# PROIECT_v21.net
KiCad netlist of a schematic drawn in EAGLE
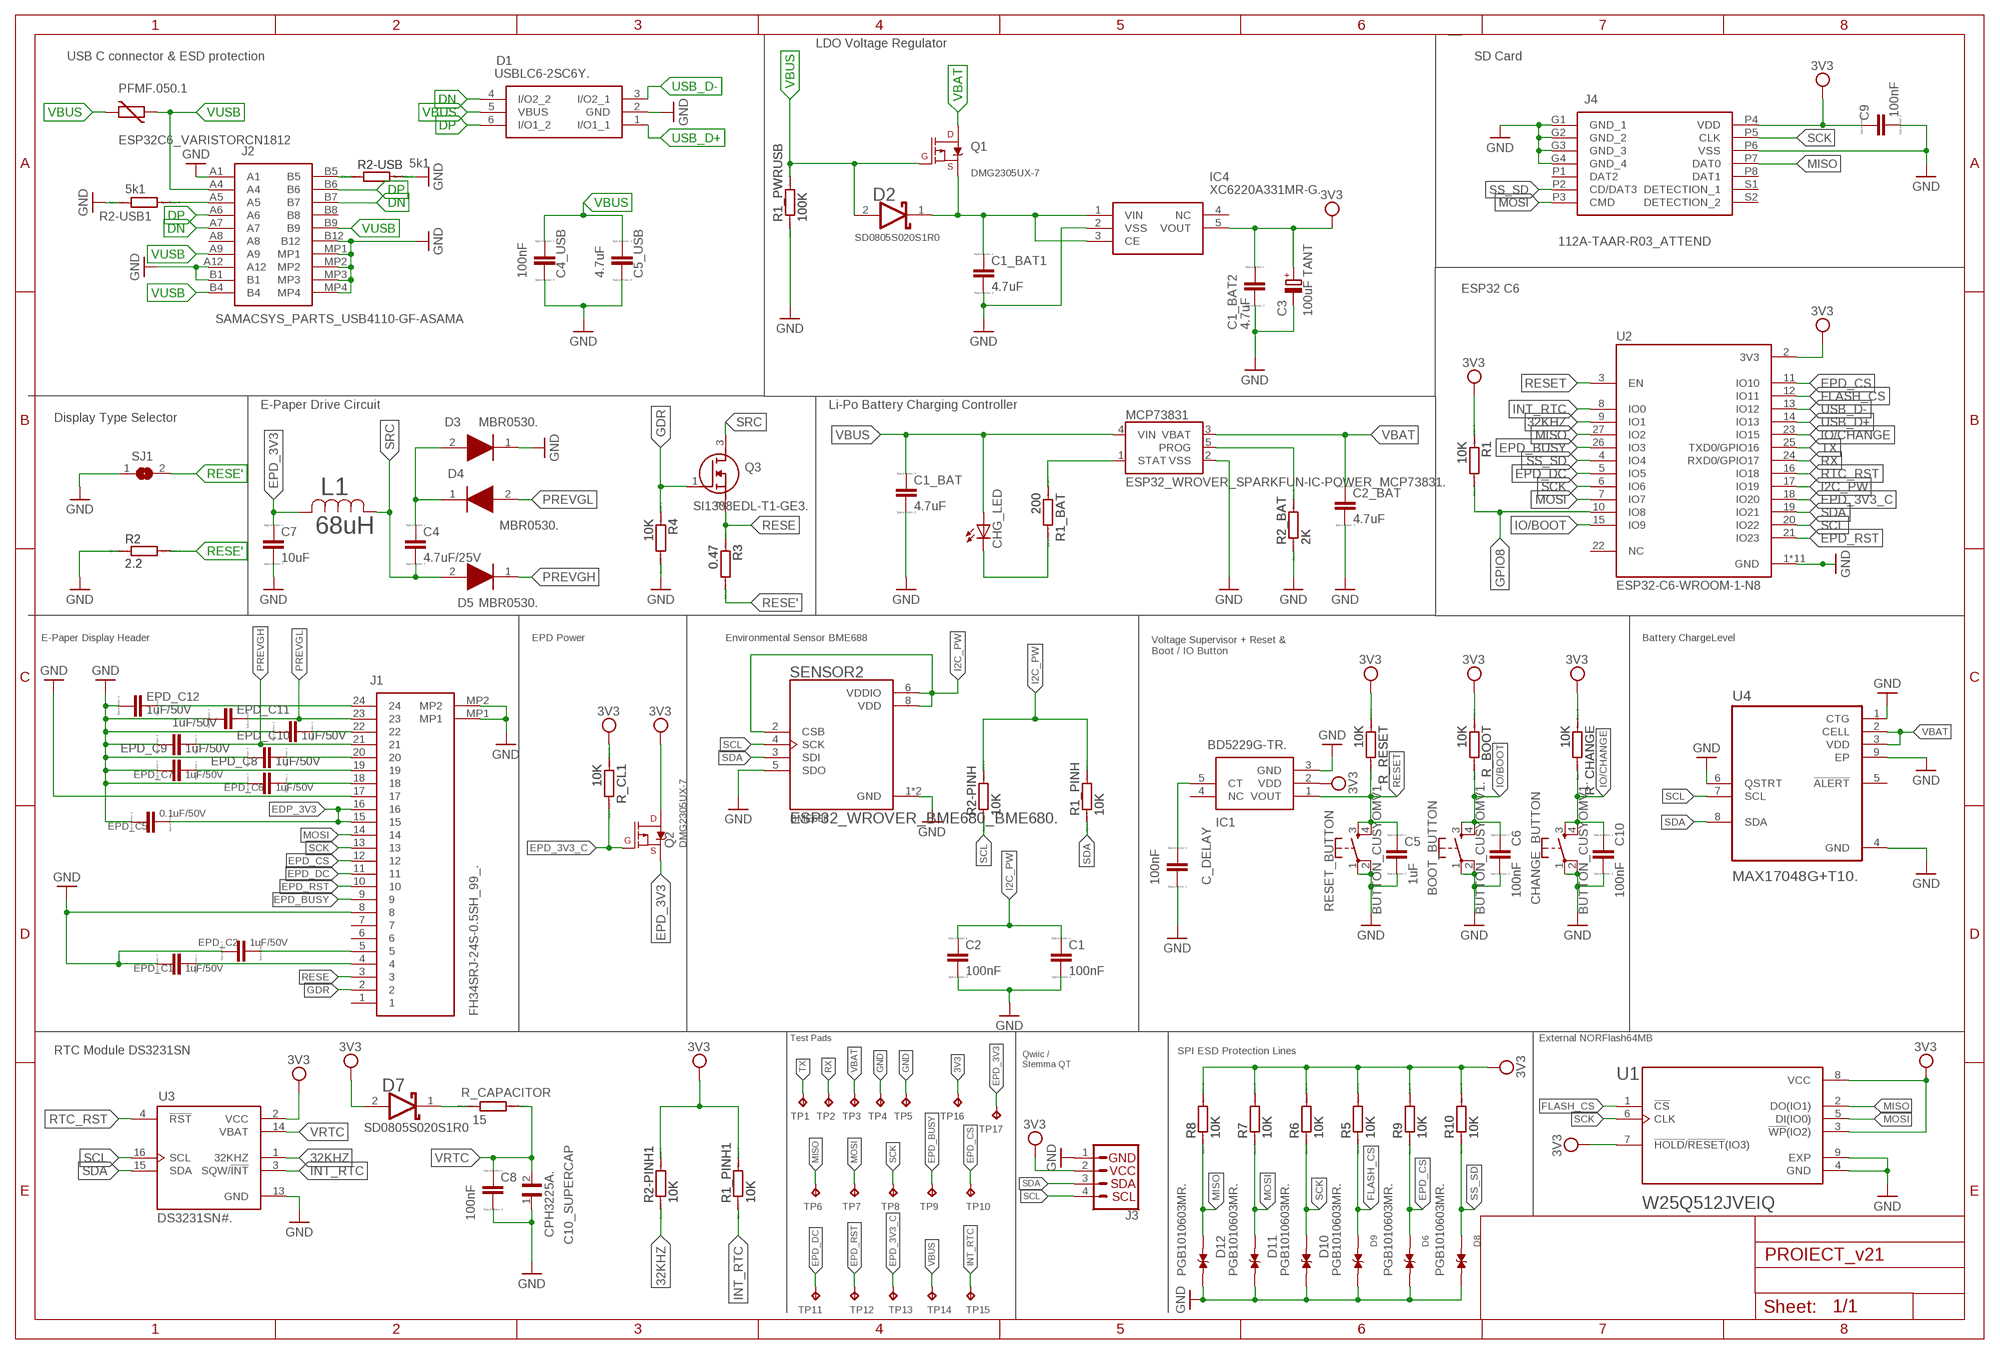
[diagram p0: schematic, sheet 1]

(export (version "E")
  (design (tool "Eeschema 10.0.6"))
  (components
    (comp (ref "BOOT_BUTTON")
      (value "BUTTON_CUSYOMV1.")
      (footprint "eagle-import:MYBUTTON")
      (libsource (lib "eagle-import") (part "BUTTON_CUSYOMV1."))
    )
    (comp (ref "C1")
      (value "100nF")
      (footprint "eagle-import:EAGLE-LTSPICE_C0402")
      (libsource (lib "eagle-import") (part "EAGLE-LTSPICE_CC0402"))
    )
    (comp (ref "C1_BAT")
      (value "4.7uF")
      (footprint "eagle-import:EAGLE-LTSPICE_C0402")
      (libsource (lib "eagle-import") (part "EAGLE-LTSPICE_CC0402"))
    )
    (comp (ref "C1_BAT1")
      (value "4.7uF")
      (footprint "eagle-import:EAGLE-LTSPICE_C0402")
      (libsource (lib "eagle-import") (part "EAGLE-LTSPICE_CC0402"))
    )
    (comp (ref "C1_BAT2")
      (value "4.7uF")
      (footprint "eagle-import:EAGLE-LTSPICE_C0402")
      (libsource (lib "eagle-import") (part "EAGLE-LTSPICE_CC0402"))
    )
    (comp (ref "C2")
      (value "100nF")
      (footprint "eagle-import:EAGLE-LTSPICE_C0402")
      (libsource (lib "eagle-import") (part "EAGLE-LTSPICE_CC0402"))
    )
    (comp (ref "C2_BAT")
      (value "4.7uF")
      (footprint "eagle-import:EAGLE-LTSPICE_C0402")
      (libsource (lib "eagle-import") (part "EAGLE-LTSPICE_CC0402"))
    )
    (comp (ref "C3")
      (value "100uF TANT")
      (footprint "eagle-import:RCL_CT3528")
      (libsource (lib "eagle-import") (part "RCL_CPOL-EUCT3528"))
    )
    (comp (ref "C4")
      (value "4.7uF/25V")
      (footprint "eagle-import:EAGLE-LTSPICE_C0402")
      (libsource (lib "eagle-import") (part "EAGLE-LTSPICE_CC0402"))
    )
    (comp (ref "C4_USB")
      (value "100nF")
      (footprint "eagle-import:EAGLE-LTSPICE_C0402")
      (libsource (lib "eagle-import") (part "EAGLE-LTSPICE_CC0402"))
    )
    (comp (ref "C5")
      (value "1uF")
      (footprint "eagle-import:EAGLE-LTSPICE_C0402")
      (libsource (lib "eagle-import") (part "EAGLE-LTSPICE_CC0402"))
    )
    (comp (ref "C5_USB")
      (value "4.7uF")
      (footprint "eagle-import:EAGLE-LTSPICE_C0402")
      (libsource (lib "eagle-import") (part "EAGLE-LTSPICE_CC0402"))
    )
    (comp (ref "C6")
      (value "100nF")
      (footprint "eagle-import:EAGLE-LTSPICE_C0402")
      (libsource (lib "eagle-import") (part "EAGLE-LTSPICE_CC0402"))
    )
    (comp (ref "C7")
      (value "10uF")
      (footprint "eagle-import:EAGLE-LTSPICE_C0402")
      (libsource (lib "eagle-import") (part "EAGLE-LTSPICE_CC0402"))
    )
    (comp (ref "C8")
      (value "100nF")
      (footprint "eagle-import:EAGLE-LTSPICE_C0402")
      (libsource (lib "eagle-import") (part "EAGLE-LTSPICE_CC0402"))
    )
    (comp (ref "C9")
      (value "100nF")
      (footprint "eagle-import:EAGLE-LTSPICE_C0402")
      (libsource (lib "eagle-import") (part "EAGLE-LTSPICE_CC0402"))
    )
    (comp (ref "C10")
      (value "100nF")
      (footprint "eagle-import:EAGLE-LTSPICE_C0402")
      (libsource (lib "eagle-import") (part "EAGLE-LTSPICE_CC0402"))
    )
    (comp (ref "C10_SUPERCAP")
      (value "CPH3225A.")
      (footprint "eagle-import:CAPCP3225X100N")
      (libsource (lib "eagle-import") (part "CPH3225A."))
    )
    (comp (ref "CHANGE_BUTTON")
      (value "BUTTON_CUSYOMV1.")
      (footprint "eagle-import:MYBUTTON")
      (libsource (lib "eagle-import") (part "BUTTON_CUSYOMV1."))
    )
    (comp (ref "CHG_LED")
      (value "ADAFRUIT_LEDCHIP-LED0603")
      (footprint "eagle-import:ADAFRUIT_CHIP-LED0603")
      (libsource (lib "eagle-import") (part "ADAFRUIT_LEDCHIP-LED0603"))
    )
    (comp (ref "C_DELAY")
      (value "100nF")
      (footprint "eagle-import:EAGLE-LTSPICE_C0402")
      (libsource (lib "eagle-import") (part "EAGLE-LTSPICE_CC0402"))
    )
    (comp (ref "D1")
      (value "USBLC6-2SC6Y.")
      (footprint "eagle-import:SOT95P280X145-6N")
      (libsource (lib "eagle-import") (part "USBLC6-2SC6Y."))
    )
    (comp (ref "D2")
      (value "ESP32_WROVER_AVX---SD0805S020S1R0_AVX_SD0805S020S1R0_0_0AVX_SD0805S020S1R0_0_0")
      (footprint "eagle-import:ESP32_WROVER_AVX---SD0805S020S1R0_AVX_SD0805S020S1R0_0")
      (fields (field (name "NUME") "SD0805S020S1R0"))
      (libsource (lib "eagle-import") (part "ESP32_WROVER_AVX---SD0805S020S1R0_AVX_SD0805S020S1R0_0_0AVX_SD0805S020S1R0_0_0"))
    )
    (comp (ref "D3")
      (value "MBR0530.")
      (footprint "eagle-import:SOD3716X135N")
      (libsource (lib "eagle-import") (part "MBR0530."))
    )
    (comp (ref "D4")
      (value "MBR0530.")
      (footprint "eagle-import:SOD3716X135N")
      (libsource (lib "eagle-import") (part "MBR0530."))
    )
    (comp (ref "D5")
      (value "MBR0530.")
      (footprint "eagle-import:SOD3716X135N")
      (libsource (lib "eagle-import") (part "MBR0530."))
    )
    (comp (ref "D6")
      (value "PGB1010603MR.")
      (footprint "eagle-import:DIOC1608X36N")
      (libsource (lib "eagle-import") (part "PGB1010603MR."))
    )
    (comp (ref "D7")
      (value "ESP32_WROVER_AVX---SD0805S020S1R0_AVX_SD0805S020S1R0_0_0AVX_SD0805S020S1R0_0_0")
      (footprint "eagle-import:ESP32_WROVER_AVX---SD0805S020S1R0_AVX_SD0805S020S1R0_0")
      (fields (field (name "NUME") "SD0805S020S1R0"))
      (libsource (lib "eagle-import") (part "ESP32_WROVER_AVX---SD0805S020S1R0_AVX_SD0805S020S1R0_0_0AVX_SD0805S020S1R0_0_0"))
    )
    (comp (ref "D8")
      (value "PGB1010603MR.")
      (footprint "eagle-import:DIOC1608X36N")
      (libsource (lib "eagle-import") (part "PGB1010603MR."))
    )
    (comp (ref "D9")
      (value "PGB1010603MR.")
      (footprint "eagle-import:DIOC1608X36N")
      (libsource (lib "eagle-import") (part "PGB1010603MR."))
    )
    (comp (ref "D10")
      (value "PGB1010603MR.")
      (footprint "eagle-import:DIOC1608X36N")
      (libsource (lib "eagle-import") (part "PGB1010603MR."))
    )
    (comp (ref "D11")
      (value "PGB1010603MR.")
      (footprint "eagle-import:DIOC1608X36N")
      (libsource (lib "eagle-import") (part "PGB1010603MR."))
    )
    (comp (ref "D12")
      (value "PGB1010603MR.")
      (footprint "eagle-import:DIOC1608X36N")
      (libsource (lib "eagle-import") (part "PGB1010603MR."))
    )
    (comp (ref "EPD_C1")
      (value "1uF/50V")
      (footprint "eagle-import:EAGLE-LTSPICE_C0402")
      (libsource (lib "eagle-import") (part "EAGLE-LTSPICE_CC0402"))
    )
    (comp (ref "EPD_C2")
      (value "1uF/50V")
      (footprint "eagle-import:EAGLE-LTSPICE_C0402")
      (libsource (lib "eagle-import") (part "EAGLE-LTSPICE_CC0402"))
    )
    (comp (ref "EPD_C5")
      (value "0.1uF/50V")
      (footprint "eagle-import:EAGLE-LTSPICE_C0402")
      (libsource (lib "eagle-import") (part "EAGLE-LTSPICE_CC0402"))
    )
    (comp (ref "EPD_C6")
      (value "1uF/50V")
      (footprint "eagle-import:EAGLE-LTSPICE_C0402")
      (libsource (lib "eagle-import") (part "EAGLE-LTSPICE_CC0402"))
    )
    (comp (ref "EPD_C7")
      (value "1uF/50V")
      (footprint "eagle-import:EAGLE-LTSPICE_C0402")
      (libsource (lib "eagle-import") (part "EAGLE-LTSPICE_CC0402"))
    )
    (comp (ref "EPD_C8")
      (value "1uF/50V")
      (footprint "eagle-import:EAGLE-LTSPICE_C0402")
      (libsource (lib "eagle-import") (part "EAGLE-LTSPICE_CC0402"))
    )
    (comp (ref "EPD_C9")
      (value "1uF/50V")
      (footprint "eagle-import:EAGLE-LTSPICE_C0402")
      (libsource (lib "eagle-import") (part "EAGLE-LTSPICE_CC0402"))
    )
    (comp (ref "EPD_C10")
      (value "1uF/50V")
      (footprint "eagle-import:EAGLE-LTSPICE_C0402")
      (libsource (lib "eagle-import") (part "EAGLE-LTSPICE_CC0402"))
    )
    (comp (ref "EPD_C11")
      (value "1uF/50V")
      (footprint "eagle-import:EAGLE-LTSPICE_C0402")
      (libsource (lib "eagle-import") (part "EAGLE-LTSPICE_CC0402"))
    )
    (comp (ref "EPD_C12")
      (value "1uF/50V")
      (footprint "eagle-import:EAGLE-LTSPICE_C0402")
      (libsource (lib "eagle-import") (part "EAGLE-LTSPICE_CC0402"))
    )
    (comp (ref "IC1")
      (value "BD5229G-TR.")
      (footprint "eagle-import:SOT95P280X125-5N")
      (libsource (lib "eagle-import") (part "BD5229G-TR."))
    )
    (comp (ref "IC4")
      (value "XC6220A331MR-G.")
      (footprint "eagle-import:SOT95P280X120-5N")
      (libsource (lib "eagle-import") (part "XC6220A331MR-G."))
    )
    (comp (ref "J1")
      (value "FH34SRJ-24S-0.5SH_99_.")
      (footprint "eagle-import:FH34SRJ24S05SH99")
      (libsource (lib "eagle-import") (part "FH34SRJ-24S-0.5SH_99_."))
    )
    (comp (ref "J2")
      (value "SAMACSYS_PARTS_USB4110-GF-ASAMA")
      (footprint "eagle-import:SAMACSYS_PARTS_USB4110GFA")
      (libsource (lib "eagle-import") (part "SAMACSYS_PARTS_USB4110-GF-ASAMA"))
    )
    (comp (ref "J3")
      (value "QWIIC_RIGHT_ANGLE")
      (footprint "eagle-import:JST04_1MM_RA")
      (libsource (lib "eagle-import") (part "QWIIC_CONNECTORJS-1MM"))
    )
    (comp (ref "J4")
      (value "112A-TAAR-R03_ATTEND")
      (footprint "eagle-import:112ATAARR03ATTEND")
      (fields (field (name "MANUFACTURER_PART_NUMBER") "112A-TAAR-R03 ATTEND"))
      (libsource (lib "eagle-import") (part "112A-TAAR-R03_ATTEND"))
    )
    (comp (ref "L1")
      (value "68uH")
      (footprint "eagle-import:IND_4828-WE-TPC_WRE")
      (libsource (lib "eagle-import") (part "744043680IND_4828-WE-TPC_WRE"))
    )
    (comp (ref "MCP73831")
      (value "ESP32_WROVER_SPARKFUN-IC-POWER_MCP73831.")
      (footprint "eagle-import:ESP32_WROVER_SPARKFUN-IC-POWER_SOT23-5")
      (libsource (lib "eagle-import") (part "ESP32_WROVER_SPARKFUN-IC-POWER_MCP73831."))
    )
    (comp (ref "PFMF.050.1")
      (value "ESP32C6_VARISTORCN1812")
      (footprint "eagle-import:ESP32C6_VARISTOR_CT_CN1812")
      (libsource (lib "eagle-import") (part "ESP32C6_VARISTORCN1812"))
    )
    (comp (ref "Q1")
      (value "20V/4.2A/52mΩ/1.4W")
      (footprint "eagle-import:ESP32_WROVER_SPARKFUN-DISCRETESEMI_SOT23-3")
      (fields (field (name "NUME") "DMG2305UX-7"))
      (libsource (lib "eagle-import") (part "ESP32_WROVER_SPARKFUN-DISCRETESEMI_MOSFET_PCH-DMG2305UX-7"))
    )
    (comp (ref "Q2")
      (value "20V/4.2A/52mΩ/1.4W")
      (footprint "eagle-import:ESP32_WROVER_SPARKFUN-DISCRETESEMI_SOT23-3")
      (fields (field (name "Q2") "DMG2305UX-7"))
      (libsource (lib "eagle-import") (part "ESP32_WROVER_SPARKFUN-DISCRETESEMI_MOSFET_PCH-DMG2305UX-7"))
    )
    (comp (ref "Q3")
      (value "SI1308EDL-T1-GE3.")
      (footprint "eagle-import:SOT65P210X110-3N")
      (libsource (lib "eagle-import") (part "SI1308EDL-T1-GE3."))
    )
    (comp (ref "R1")
      (value "10K")
      (footprint "eagle-import:ESP32_WROVER_EAGLE-LTSPICE_R0402")
      (libsource (lib "eagle-import") (part "ESP32_WROVER_EAGLE-LTSPICE_RR0402"))
    )
    (comp (ref "R1_BAT")
      (value "200")
      (footprint "eagle-import:ESP32_WROVER_EAGLE-LTSPICE_R0402")
      (libsource (lib "eagle-import") (part "ESP32_WROVER_EAGLE-LTSPICE_RR0402"))
    )
    (comp (ref "R1_PINH")
      (value "10K")
      (footprint "eagle-import:ESP32_WROVER_EAGLE-LTSPICE_R0402")
      (libsource (lib "eagle-import") (part "ESP32_WROVER_EAGLE-LTSPICE_RR0402"))
    )
    (comp (ref "R1_PINH1")
      (value "10K")
      (footprint "eagle-import:ESP32_WROVER_EAGLE-LTSPICE_R0402")
      (libsource (lib "eagle-import") (part "ESP32_WROVER_EAGLE-LTSPICE_RR0402"))
    )
    (comp (ref "R1_PWRUSB")
      (value "100K")
      (footprint "eagle-import:ESP32_WROVER_EAGLE-LTSPICE_R0402")
      (libsource (lib "eagle-import") (part "ESP32_WROVER_EAGLE-LTSPICE_RR0402"))
    )
    (comp (ref "R2")
      (value "2.2")
      (footprint "eagle-import:ESP32_WROVER_EAGLE-LTSPICE_R0402")
      (libsource (lib "eagle-import") (part "ESP32_WROVER_EAGLE-LTSPICE_RR0402"))
    )
    (comp (ref "R2-PINH")
      (value "10K")
      (footprint "eagle-import:ESP32_WROVER_EAGLE-LTSPICE_R0402")
      (libsource (lib "eagle-import") (part "ESP32_WROVER_EAGLE-LTSPICE_RR0402"))
    )
    (comp (ref "R2-PINH1")
      (value "10K")
      (footprint "eagle-import:ESP32_WROVER_EAGLE-LTSPICE_R0402")
      (libsource (lib "eagle-import") (part "ESP32_WROVER_EAGLE-LTSPICE_RR0402"))
    )
    (comp (ref "R2-USB")
      (value "5k1")
      (footprint "eagle-import:ESP32_WROVER_EAGLE-LTSPICE_R0402")
      (libsource (lib "eagle-import") (part "ESP32_WROVER_EAGLE-LTSPICE_RR0402"))
    )
    (comp (ref "R2-USB1")
      (value "5k1")
      (footprint "eagle-import:ESP32_WROVER_EAGLE-LTSPICE_R0402")
      (libsource (lib "eagle-import") (part "ESP32_WROVER_EAGLE-LTSPICE_RR0402"))
    )
    (comp (ref "R2_BAT")
      (value "2K")
      (footprint "eagle-import:ESP32_WROVER_EAGLE-LTSPICE_R0402")
      (libsource (lib "eagle-import") (part "ESP32_WROVER_EAGLE-LTSPICE_RR0402"))
    )
    (comp (ref "R3")
      (value "0.47")
      (footprint "eagle-import:ESP32_WROVER_EAGLE-LTSPICE_R0402")
      (libsource (lib "eagle-import") (part "ESP32_WROVER_EAGLE-LTSPICE_RR0402"))
    )
    (comp (ref "R4")
      (value "10K")
      (footprint "eagle-import:ESP32_WROVER_EAGLE-LTSPICE_R0402")
      (libsource (lib "eagle-import") (part "ESP32_WROVER_EAGLE-LTSPICE_RR0402"))
    )
    (comp (ref "R5")
      (value "10K")
      (footprint "eagle-import:ESP32_WROVER_EAGLE-LTSPICE_R0402")
      (libsource (lib "eagle-import") (part "ESP32_WROVER_EAGLE-LTSPICE_RR0402"))
    )
    (comp (ref "R6")
      (value "10K")
      (footprint "eagle-import:ESP32_WROVER_EAGLE-LTSPICE_R0402")
      (libsource (lib "eagle-import") (part "ESP32_WROVER_EAGLE-LTSPICE_RR0402"))
    )
    (comp (ref "R7")
      (value "10K")
      (footprint "eagle-import:ESP32_WROVER_EAGLE-LTSPICE_R0402")
      (libsource (lib "eagle-import") (part "ESP32_WROVER_EAGLE-LTSPICE_RR0402"))
    )
    (comp (ref "R8")
      (value "10K")
      (footprint "eagle-import:ESP32_WROVER_EAGLE-LTSPICE_R0402")
      (libsource (lib "eagle-import") (part "ESP32_WROVER_EAGLE-LTSPICE_RR0402"))
    )
    (comp (ref "R9")
      (value "10K")
      (footprint "eagle-import:ESP32_WROVER_EAGLE-LTSPICE_R0402")
      (libsource (lib "eagle-import") (part "ESP32_WROVER_EAGLE-LTSPICE_RR0402"))
    )
    (comp (ref "R10")
      (value "10K")
      (footprint "eagle-import:ESP32_WROVER_EAGLE-LTSPICE_R0402")
      (libsource (lib "eagle-import") (part "ESP32_WROVER_EAGLE-LTSPICE_RR0402"))
    )
    (comp (ref "RESET_BUTTON")
      (value "BUTTON_CUSYOMV1.")
      (footprint "eagle-import:MYBUTTON")
      (libsource (lib "eagle-import") (part "BUTTON_CUSYOMV1."))
    )
    (comp (ref "R_BOOT")
      (value "10K")
      (footprint "eagle-import:ESP32_WROVER_EAGLE-LTSPICE_R0402")
      (libsource (lib "eagle-import") (part "ESP32_WROVER_EAGLE-LTSPICE_RR0402"))
    )
    (comp (ref "R_CAPACITOR")
      (value "15")
      (footprint "eagle-import:ESP32_WROVER_EAGLE-LTSPICE_R0402")
      (libsource (lib "eagle-import") (part "ESP32_WROVER_EAGLE-LTSPICE_RR0402"))
    )
    (comp (ref "R_CHANGE")
      (value "10K")
      (footprint "eagle-import:ESP32_WROVER_EAGLE-LTSPICE_R0402")
      (libsource (lib "eagle-import") (part "ESP32_WROVER_EAGLE-LTSPICE_RR0402"))
    )
    (comp (ref "R_CL1")
      (value "10K")
      (footprint "eagle-import:ESP32_WROVER_EAGLE-LTSPICE_R0402")
      (libsource (lib "eagle-import") (part "ESP32_WROVER_EAGLE-LTSPICE_RR0402"))
    )
    (comp (ref "R_RESET")
      (value "10K")
      (footprint "eagle-import:ESP32_WROVER_EAGLE-LTSPICE_R0402")
      (libsource (lib "eagle-import") (part "ESP32_WROVER_EAGLE-LTSPICE_RR0402"))
    )
    (comp (ref "SENSOR2")
      (value "ESP32_WROVER_BME680_BME680.")
      (footprint "eagle-import:ESP32_WROVER_BME680_PSON80P300X300X100-8N")
      (fields (field (name "NUME") "BME688"))
      (libsource (lib "eagle-import") (part "ESP32_WROVER_BME680_BME680."))
    )
    (comp (ref "SJ1")
      (value "SJ.")
      (footprint "eagle-import:SJ")
      (libsource (lib "eagle-import") (part "SJ."))
    )
    (comp (ref "TP1")
      (value "TPTP20R")
      (footprint "eagle-import:TP20R")
      (libsource (lib "eagle-import") (part "TPTP20R"))
    )
    (comp (ref "TP2")
      (value "TPTP20R")
      (footprint "eagle-import:TP20R")
      (libsource (lib "eagle-import") (part "TPTP20R"))
    )
    (comp (ref "TP3")
      (value "TPTP20R")
      (footprint "eagle-import:TP20R")
      (libsource (lib "eagle-import") (part "TPTP20R"))
    )
    (comp (ref "TP4")
      (value "TPTP20R")
      (footprint "eagle-import:TP20R")
      (libsource (lib "eagle-import") (part "TPTP20R"))
    )
    (comp (ref "TP5")
      (value "TPTP20R")
      (footprint "eagle-import:TP20R")
      (libsource (lib "eagle-import") (part "TPTP20R"))
    )
    (comp (ref "TP6")
      (value "TPTP20R")
      (footprint "eagle-import:TP20R")
      (libsource (lib "eagle-import") (part "TPTP20R"))
    )
    (comp (ref "TP7")
      (value "TPTP20R")
      (footprint "eagle-import:TP20R")
      (libsource (lib "eagle-import") (part "TPTP20R"))
    )
    (comp (ref "TP8")
      (value "TPTP20R")
      (footprint "eagle-import:TP20R")
      (libsource (lib "eagle-import") (part "TPTP20R"))
    )
    (comp (ref "TP9")
      (value "TPTP20R")
      (footprint "eagle-import:TP20R")
      (libsource (lib "eagle-import") (part "TPTP20R"))
    )
    (comp (ref "TP10")
      (value "TPTP20R")
      (footprint "eagle-import:TP20R")
      (libsource (lib "eagle-import") (part "TPTP20R"))
    )
    (comp (ref "TP11")
      (value "TPTP20R")
      (footprint "eagle-import:TP20R")
      (libsource (lib "eagle-import") (part "TPTP20R"))
    )
    (comp (ref "TP12")
      (value "TPTP20R")
      (footprint "eagle-import:TP20R")
      (libsource (lib "eagle-import") (part "TPTP20R"))
    )
    (comp (ref "TP13")
      (value "TPTP20R")
      (footprint "eagle-import:TP20R")
      (libsource (lib "eagle-import") (part "TPTP20R"))
    )
    (comp (ref "TP14")
      (value "TPTP20R")
      (footprint "eagle-import:TP20R")
      (libsource (lib "eagle-import") (part "TPTP20R"))
    )
    (comp (ref "TP15")
      (value "TPTP20R")
      (footprint "eagle-import:TP20R")
      (libsource (lib "eagle-import") (part "TPTP20R"))
    )
    (comp (ref "TP16")
      (value "TPTP20R")
      (footprint "eagle-import:TP20R")
      (libsource (lib "eagle-import") (part "TPTP20R"))
    )
    (comp (ref "TP17")
      (value "TPTP20R")
      (footprint "eagle-import:TP20R")
      (libsource (lib "eagle-import") (part "TPTP20R"))
    )
    (comp (ref "U1")
      (value "W25Q512JVEIQ")
      (footprint "eagle-import:SON127P600X800X80-9N")
      (fields (field (name "MF") "Winbond Electronics"))
      (libsource (lib "eagle-import") (part "W25Q512JVEIQ"))
    )
    (comp (ref "U2")
      (value "ESP32-C6-WROOM-1-N8")
      (footprint "eagle-import:XCVR_ESP32-C6-WROOM-1-N8")
      (fields (field (name "MF") "Espressif Systems"))
      (libsource (lib "eagle-import") (part "ESP32-C6-WROOM-1-N8"))
    )
    (comp (ref "U3")
      (value "DS3231SN#.")
      (footprint "eagle-import:SOIC127P1032X265-16N")
      (libsource (lib "eagle-import") (part "DS3231SN#."))
    )
    (comp (ref "U4")
      (value "MAX17048G+T10.")
      (footprint "eagle-import:SON50P200X200X80-9N")
      (libsource (lib "eagle-import") (part "MAX17048G+T10."))
    )
  )
  (nets
    (net (code "1") (name "3V3") (class "Default")
      (node (ref "C1_BAT2") (pin "1") (pinfunction "1_1") (pintype "passive"))
      (node (ref "C3") (pin "+") (pinfunction "+_+") (pintype "passive"))
      (node (ref "C9") (pin "1") (pinfunction "1_1") (pintype "passive"))
      (node (ref "D7") (pin "2") (pinfunction "ANODE_2") (pintype "bidirectional"))
      (node (ref "IC1") (pin "2") (pinfunction "VDD_2") (pintype "bidirectional"))
      (node (ref "IC4") (pin "5") (pinfunction "VOUT_5") (pintype "bidirectional"))
      (node (ref "J3") (pin "2") (pinfunction "2_2") (pintype "power_in"))
      (node (ref "J4") (pin "P4") (pinfunction "VDD_P4") (pintype "bidirectional"))
      (node (ref "Q2") (pin "3") (pinfunction "D_3") (pintype "bidirectional"))
      (node (ref "R1") (pin "1") (pinfunction "1_1") (pintype "passive"))
      (node (ref "R10") (pin "2") (pinfunction "2_2") (pintype "passive"))
      (node (ref "R1_PINH1") (pin "2") (pinfunction "2_2") (pintype "passive"))
      (node (ref "R2-PINH1") (pin "2") (pinfunction "2_2") (pintype "passive"))
      (node (ref "R5") (pin "2") (pinfunction "2_2") (pintype "passive"))
      (node (ref "R6") (pin "2") (pinfunction "2_2") (pintype "passive"))
      (node (ref "R7") (pin "2") (pinfunction "2_2") (pintype "passive"))
      (node (ref "R8") (pin "2") (pinfunction "2_2") (pintype "passive"))
      (node (ref "R9") (pin "2") (pinfunction "2_2") (pintype "passive"))
      (node (ref "R_BOOT") (pin "1") (pinfunction "1_1") (pintype "passive"))
      (node (ref "R_CHANGE") (pin "1") (pinfunction "1_1") (pintype "passive"))
      (node (ref "R_CL1") (pin "1") (pinfunction "1_1") (pintype "passive"))
      (node (ref "R_RESET") (pin "1") (pinfunction "1_1") (pintype "passive"))
      (node (ref "TP16") (pin "TP") (pinfunction "TP_TP") (pintype "input"))
      (node (ref "U1") (pin "3") (pinfunction "~{WP}(IO2)_3") (pintype "bidirectional"))
      (node (ref "U1") (pin "7") (pinfunction "~{HOLD}/~{RESET}(IO3)_7") (pintype "bidirectional"))
      (node (ref "U1") (pin "8") (pinfunction "VCC_8") (pintype "power_in"))
      (node (ref "U2") (pin "2") (pinfunction "3V3_2") (pintype "power_in"))
      (node (ref "U3") (pin "2") (pinfunction "VCC_2") (pintype "power_in"))
    )
    (net (code "2") (name "32KHZ") (class "Default")
      (node (ref "R2-PINH1") (pin "1") (pinfunction "1_1") (pintype "passive"))
      (node (ref "U2") (pin "9") (pinfunction "IO1_9") (pintype "bidirectional"))
      (node (ref "U3") (pin "1") (pinfunction "32KHZ_1") (pintype "output"))
    )
    (net (code "3") (name "DN") (class "Default")
      (node (ref "D1") (pin "4") (pinfunction "I/O2_2_4") (pintype "bidirectional"))
      (node (ref "J2") (pin "A7") (pinfunction "A7_A7") (pintype "bidirectional"))
      (node (ref "J2") (pin "B7") (pinfunction "B7_B7") (pintype "bidirectional"))
    )
    (net (code "4") (name "DP") (class "Default")
      (node (ref "D1") (pin "6") (pinfunction "I/O1_2_6") (pintype "bidirectional"))
      (node (ref "J2") (pin "A6") (pinfunction "A6_A6") (pintype "bidirectional"))
      (node (ref "J2") (pin "B6") (pinfunction "B6_B6") (pintype "bidirectional"))
    )
    (net (code "5") (name "EDP_3V3") (class "Default")
      (node (ref "EPD_C5") (pin "1") (pinfunction "1_1") (pintype "passive"))
      (node (ref "J1") (pin "15") (pinfunction "15_15") (pintype "bidirectional"))
      (node (ref "J1") (pin "16") (pinfunction "16_16") (pintype "bidirectional"))
    )
    (net (code "6") (name "EPD_3V3") (class "Default")
      (node (ref "C7") (pin "1") (pinfunction "1_1") (pintype "passive"))
      (node (ref "L1") (pin "2") (pinfunction "2_2") (pintype "passive"))
      (node (ref "Q2") (pin "2") (pinfunction "S_2") (pintype "bidirectional"))
      (node (ref "TP17") (pin "TP") (pinfunction "TP_TP") (pintype "input"))
    )
    (net (code "7") (name "EPD_3V3_C") (class "Default")
      (node (ref "Q2") (pin "1") (pinfunction "G_1") (pintype "bidirectional"))
      (node (ref "R_CL1") (pin "2") (pinfunction "2_2") (pintype "passive"))
      (node (ref "TP13") (pin "TP") (pinfunction "TP_TP") (pintype "input"))
      (node (ref "U2") (pin "18") (pinfunction "IO20_18") (pintype "bidirectional"))
    )
    (net (code "8") (name "EPD_BUSY") (class "Default")
      (node (ref "J1") (pin "9") (pinfunction "9_9") (pintype "bidirectional"))
      (node (ref "TP9") (pin "TP") (pinfunction "TP_TP") (pintype "input"))
      (node (ref "U2") (pin "26") (pinfunction "IO3_26") (pintype "bidirectional"))
    )
    (net (code "9") (name "EPD_CS") (class "Default")
      (node (ref "D6") (pin "1") (pinfunction "1_1") (pintype "passive"))
      (node (ref "J1") (pin "12") (pinfunction "12_12") (pintype "bidirectional"))
      (node (ref "R9") (pin "1") (pinfunction "1_1") (pintype "passive"))
      (node (ref "TP10") (pin "TP") (pinfunction "TP_TP") (pintype "input"))
      (node (ref "U2") (pin "11") (pinfunction "IO10_11") (pintype "bidirectional"))
    )
    (net (code "10") (name "EPD_DC") (class "Default")
      (node (ref "J1") (pin "11") (pinfunction "11_11") (pintype "bidirectional"))
      (node (ref "TP11") (pin "TP") (pinfunction "TP_TP") (pintype "input"))
      (node (ref "U2") (pin "5") (pinfunction "IO5_5") (pintype "bidirectional"))
    )
    (net (code "11") (name "EPD_RST") (class "Default")
      (node (ref "J1") (pin "10") (pinfunction "10_10") (pintype "bidirectional"))
      (node (ref "TP12") (pin "TP") (pinfunction "TP_TP") (pintype "input"))
      (node (ref "U2") (pin "21") (pinfunction "IO23_21") (pintype "bidirectional"))
    )
    (net (code "12") (name "FLASH_CS") (class "Default")
      (node (ref "D9") (pin "1") (pinfunction "1_1") (pintype "passive"))
      (node (ref "R5") (pin "1") (pinfunction "1_1") (pintype "passive"))
      (node (ref "U1") (pin "1") (pinfunction "~{CS}_1") (pintype "input"))
      (node (ref "U2") (pin "12") (pinfunction "IO11_12") (pintype "bidirectional"))
    )
    (net (code "13") (name "GDR") (class "Default")
      (node (ref "J1") (pin "2") (pinfunction "2_2") (pintype "bidirectional"))
      (node (ref "Q3") (pin "1") (pinfunction "G_1") (pintype "bidirectional"))
      (node (ref "R4") (pin "1") (pinfunction "1_1") (pintype "passive"))
    )
    (net (code "14") (name "GND") (class "Default")
      (node (ref "BOOT_BUTTON") (pin "1") (pinfunction "1_1") (pintype "passive"))
      (node (ref "BOOT_BUTTON") (pin "2") (pinfunction "2_2") (pintype "passive"))
      (node (ref "C1") (pin "2") (pinfunction "2_2") (pintype "passive"))
      (node (ref "C10") (pin "2") (pinfunction "2_2") (pintype "passive"))
      (node (ref "C10_SUPERCAP") (pin "1") (pinfunction "1_1") (pintype "passive"))
      (node (ref "C1_BAT") (pin "2") (pinfunction "2_2") (pintype "passive"))
      (node (ref "C1_BAT1") (pin "2") (pinfunction "2_2") (pintype "passive"))
      (node (ref "C1_BAT2") (pin "2") (pinfunction "2_2") (pintype "passive"))
      (node (ref "C2") (pin "2") (pinfunction "2_2") (pintype "passive"))
      (node (ref "C2_BAT") (pin "2") (pinfunction "2_2") (pintype "passive"))
      (node (ref "C3") (pin "-") (pinfunction "-_-") (pintype "passive"))
      (node (ref "C4_USB") (pin "2") (pinfunction "2_2") (pintype "passive"))
      (node (ref "C5") (pin "2") (pinfunction "2_2") (pintype "passive"))
      (node (ref "C5_USB") (pin "2") (pinfunction "2_2") (pintype "passive"))
      (node (ref "C6") (pin "2") (pinfunction "2_2") (pintype "passive"))
      (node (ref "C7") (pin "2") (pinfunction "2_2") (pintype "passive"))
      (node (ref "C8") (pin "2") (pinfunction "2_2") (pintype "passive"))
      (node (ref "C9") (pin "2") (pinfunction "2_2") (pintype "passive"))
      (node (ref "CHANGE_BUTTON") (pin "1") (pinfunction "1_1") (pintype "passive"))
      (node (ref "CHANGE_BUTTON") (pin "2") (pinfunction "2_2") (pintype "passive"))
      (node (ref "C_DELAY") (pin "2") (pinfunction "2_2") (pintype "passive"))
      (node (ref "D1") (pin "2") (pinfunction "GND_2") (pintype "bidirectional"))
      (node (ref "D10") (pin "2") (pinfunction "2_2") (pintype "passive"))
      (node (ref "D11") (pin "2") (pinfunction "2_2") (pintype "passive"))
      (node (ref "D12") (pin "2") (pinfunction "2_2") (pintype "passive"))
      (node (ref "D3") (pin "1") (pinfunction "K_1") (pintype "bidirectional"))
      (node (ref "D6") (pin "2") (pinfunction "2_2") (pintype "passive"))
      (node (ref "D8") (pin "2") (pinfunction "2_2") (pintype "passive"))
      (node (ref "D9") (pin "2") (pinfunction "2_2") (pintype "passive"))
      (node (ref "EPD_C1") (pin "2") (pinfunction "2_2") (pintype "passive"))
      (node (ref "EPD_C10") (pin "2") (pinfunction "2_2") (pintype "passive"))
      (node (ref "EPD_C11") (pin "2") (pinfunction "2_2") (pintype "passive"))
      (node (ref "EPD_C12") (pin "2") (pinfunction "2_2") (pintype "passive"))
      (node (ref "EPD_C2") (pin "2") (pinfunction "2_2") (pintype "passive"))
      (node (ref "EPD_C5") (pin "2") (pinfunction "2_2") (pintype "passive"))
      (node (ref "EPD_C6") (pin "2") (pinfunction "2_2") (pintype "passive"))
      (node (ref "EPD_C7") (pin "2") (pinfunction "2_2") (pintype "passive"))
      (node (ref "EPD_C8") (pin "2") (pinfunction "2_2") (pintype "passive"))
      (node (ref "EPD_C9") (pin "2") (pinfunction "2_2") (pintype "passive"))
      (node (ref "IC1") (pin "3") (pinfunction "GND_3") (pintype "bidirectional"))
      (node (ref "IC4") (pin "2") (pinfunction "VSS_2") (pintype "bidirectional"))
      (node (ref "J1") (pin "17") (pinfunction "17_17") (pintype "bidirectional"))
      (node (ref "J1") (pin "8") (pinfunction "8_8") (pintype "bidirectional"))
      (node (ref "J1") (pin "MP1") (pinfunction "MP1_MP1") (pintype "bidirectional"))
      (node (ref "J1") (pin "MP2") (pinfunction "MP2_MP2") (pintype "bidirectional"))
      (node (ref "J2") (pin "A1") (pinfunction "A1_A1") (pintype "bidirectional"))
      (node (ref "J2") (pin "A12") (pinfunction "A12_A12") (pintype "bidirectional"))
      (node (ref "J2") (pin "B1") (pinfunction "B1_B1") (pintype "bidirectional"))
      (node (ref "J2") (pin "B12") (pinfunction "B12_B12") (pintype "bidirectional"))
      (node (ref "J2") (pin "MP1") (pinfunction "MP1_MP1") (pintype "bidirectional"))
      (node (ref "J2") (pin "MP2") (pinfunction "MP2_MP2") (pintype "bidirectional"))
      (node (ref "J2") (pin "MP3") (pinfunction "MP3_MP3") (pintype "bidirectional"))
      (node (ref "J2") (pin "MP4") (pinfunction "MP4_MP4") (pintype "bidirectional"))
      (node (ref "J3") (pin "1") (pinfunction "1_1") (pintype "power_in"))
      (node (ref "J4") (pin "G1") (pinfunction "GND_1_G1") (pintype "bidirectional"))
      (node (ref "J4") (pin "G2") (pinfunction "GND_2_G2") (pintype "bidirectional"))
      (node (ref "J4") (pin "G3") (pinfunction "GND_3_G3") (pintype "bidirectional"))
      (node (ref "J4") (pin "G4") (pinfunction "GND_4_G4") (pintype "bidirectional"))
      (node (ref "J4") (pin "P6") (pinfunction "VSS_P6") (pintype "bidirectional"))
      (node (ref "MCP73831") (pin "2") (pinfunction "VSS_2") (pintype "power_in"))
      (node (ref "R1_PWRUSB") (pin "1") (pinfunction "1_1") (pintype "passive"))
      (node (ref "R2") (pin "1") (pinfunction "1_1") (pintype "passive"))
      (node (ref "R2-USB") (pin "2") (pinfunction "2_2") (pintype "passive"))
      (node (ref "R2-USB1") (pin "1") (pinfunction "1_1") (pintype "passive"))
      (node (ref "R2_BAT") (pin "1") (pinfunction "1_1") (pintype "passive"))
      (node (ref "R4") (pin "2") (pinfunction "2_2") (pintype "passive"))
      (node (ref "RESET_BUTTON") (pin "1") (pinfunction "1_1") (pintype "passive"))
      (node (ref "RESET_BUTTON") (pin "2") (pinfunction "2_2") (pintype "passive"))
      (node (ref "SENSOR2") (pin "1") (pinfunction "GND_1") (pintype "power_in"))
      (node (ref "SENSOR2") (pin "5") (pinfunction "SDO_5") (pintype "bidirectional"))
      (node (ref "SENSOR2") (pin "7") (pinfunction "GND_7") (pintype "power_in"))
      (node (ref "SJ1") (pin "1") (pinfunction "1_1") (pintype "passive"))
      (node (ref "TP4") (pin "TP") (pinfunction "TP_TP") (pintype "input"))
      (node (ref "TP5") (pin "TP") (pinfunction "TP_TP") (pintype "input"))
      (node (ref "U1") (pin "4") (pinfunction "GND_4") (pintype "power_in"))
      (node (ref "U1") (pin "9") (pinfunction "EXP_9") (pintype "passive"))
      (node (ref "U2") (pin "1") (pinfunction "GND_1") (pintype "power_in"))
      (node (ref "U2") (pin "28") (pinfunction "GND_28") (pintype "power_in"))
      (node (ref "U2") (pin "29_1") (pinfunction "GND_29_1") (pintype "power_in"))
      (node (ref "U2") (pin "29_2") (pinfunction "GND_29_2") (pintype "power_in"))
      (node (ref "U2") (pin "29_3") (pinfunction "GND_29_3") (pintype "power_in"))
      (node (ref "U2") (pin "29_4") (pinfunction "GND_29_4") (pintype "power_in"))
      (node (ref "U2") (pin "29_5") (pinfunction "GND_29_5") (pintype "power_in"))
      (node (ref "U2") (pin "29_6") (pinfunction "GND_29_6") (pintype "power_in"))
      (node (ref "U2") (pin "29_7") (pinfunction "GND_29_7") (pintype "power_in"))
      (node (ref "U2") (pin "29_8") (pinfunction "GND_29_8") (pintype "power_in"))
      (node (ref "U2") (pin "29_9") (pinfunction "GND_29_9") (pintype "power_in"))
      (node (ref "U3") (pin "13") (pinfunction "GND_13") (pintype "power_in"))
      (node (ref "U4") (pin "1") (pinfunction "CTG_1") (pintype "power_in"))
      (node (ref "U4") (pin "4") (pinfunction "GND_4") (pintype "power_in"))
      (node (ref "U4") (pin "6") (pinfunction "QSTRT_6") (pintype "input"))
      (node (ref "U4") (pin "9") (pinfunction "EP_9") (pintype "power_in"))
    )
    (net (code "15") (name "GPIO8") (class "Default")
      (node (ref "R1") (pin "2") (pinfunction "2_2") (pintype "passive"))
      (node (ref "U2") (pin "10") (pinfunction "IO8_10") (pintype "bidirectional"))
    )
    (net (code "16") (name "I2C_PW") (class "Default")
      (node (ref "C1") (pin "1") (pinfunction "1_1") (pintype "passive"))
      (node (ref "C2") (pin "1") (pinfunction "1_1") (pintype "passive"))
      (node (ref "R1_PINH") (pin "2") (pinfunction "2_2") (pintype "passive"))
      (node (ref "R2-PINH") (pin "2") (pinfunction "2_2") (pintype "passive"))
      (node (ref "SENSOR2") (pin "2") (pinfunction "CSB_2") (pintype "input"))
      (node (ref "SENSOR2") (pin "6") (pinfunction "VDDIO_6") (pintype "power_in"))
      (node (ref "SENSOR2") (pin "8") (pinfunction "VDD_8") (pintype "power_in"))
      (node (ref "U2") (pin "17") (pinfunction "IO19_17") (pintype "bidirectional"))
    )
    (net (code "17") (name "INT_RTC") (class "Default")
      (node (ref "R1_PINH1") (pin "1") (pinfunction "1_1") (pintype "passive"))
      (node (ref "TP15") (pin "TP") (pinfunction "TP_TP") (pintype "input"))
      (node (ref "U2") (pin "8") (pinfunction "IO0_8") (pintype "bidirectional"))
      (node (ref "U3") (pin "3") (pinfunction "SQW/~{INT}_3") (pintype "output"))
    )
    (net (code "18") (name "IO{slash}BOOT") (class "Default")
      (node (ref "BOOT_BUTTON") (pin "3") (pinfunction "3_3") (pintype "passive"))
      (node (ref "BOOT_BUTTON") (pin "4") (pinfunction "4_4") (pintype "passive"))
      (node (ref "C6") (pin "1") (pinfunction "1_1") (pintype "passive"))
      (node (ref "R_BOOT") (pin "2") (pinfunction "2_2") (pintype "passive"))
      (node (ref "U2") (pin "15") (pinfunction "IO9_15") (pintype "bidirectional"))
    )
    (net (code "19") (name "IO{slash}CHANGE") (class "Default")
      (node (ref "C10") (pin "1") (pinfunction "1_1") (pintype "passive"))
      (node (ref "CHANGE_BUTTON") (pin "3") (pinfunction "3_3") (pintype "passive"))
      (node (ref "CHANGE_BUTTON") (pin "4") (pinfunction "4_4") (pintype "passive"))
      (node (ref "R_CHANGE") (pin "2") (pinfunction "2_2") (pintype "passive"))
      (node (ref "U2") (pin "23") (pinfunction "IO15_23") (pintype "bidirectional"))
    )
    (net (code "20") (name "MISO") (class "Default")
      (node (ref "D12") (pin "1") (pinfunction "1_1") (pintype "passive"))
      (node (ref "J4") (pin "P7") (pinfunction "DAT0_P7") (pintype "bidirectional"))
      (node (ref "R8") (pin "1") (pinfunction "1_1") (pintype "passive"))
      (node (ref "TP6") (pin "TP") (pinfunction "TP_TP") (pintype "input"))
      (node (ref "U1") (pin "2") (pinfunction "DO(IO1)_2") (pintype "bidirectional"))
      (node (ref "U2") (pin "27") (pinfunction "IO2_27") (pintype "bidirectional"))
    )
    (net (code "21") (name "MOSI") (class "Default")
      (node (ref "D11") (pin "1") (pinfunction "1_1") (pintype "passive"))
      (node (ref "J1") (pin "14") (pinfunction "14_14") (pintype "bidirectional"))
      (node (ref "J4") (pin "P3") (pinfunction "CMD_P3") (pintype "bidirectional"))
      (node (ref "R7") (pin "1") (pinfunction "1_1") (pintype "passive"))
      (node (ref "TP7") (pin "TP") (pinfunction "TP_TP") (pintype "input"))
      (node (ref "U1") (pin "5") (pinfunction "DI(IO0)_5") (pintype "bidirectional"))
      (node (ref "U2") (pin "7") (pinfunction "IO7_7") (pintype "bidirectional"))
    )
    (net (code "22") (name "Net-(CHG_LED-PadC)") (class "Default")
      (node (ref "CHG_LED") (pin "C") (pinfunction "C_C") (pintype "passive"))
      (node (ref "R1_BAT") (pin "2") (pinfunction "2_2") (pintype "passive"))
    )
    (net (code "23") (name "Net-(D2-CATHODE)") (class "Default")
      (node (ref "C1_BAT1") (pin "1") (pinfunction "1_1") (pintype "passive"))
      (node (ref "D2") (pin "1") (pinfunction "CATHODE_1") (pintype "bidirectional"))
      (node (ref "IC4") (pin "1") (pinfunction "VIN_1") (pintype "bidirectional"))
      (node (ref "IC4") (pin "3") (pinfunction "CE_3") (pintype "bidirectional"))
      (node (ref "Q1") (pin "2") (pinfunction "S_2") (pintype "bidirectional"))
    )
    (net (code "24") (name "Net-(D3-A)") (class "Default")
      (node (ref "C4") (pin "1") (pinfunction "1_1") (pintype "passive"))
      (node (ref "D3") (pin "2") (pinfunction "A_2") (pintype "bidirectional"))
      (node (ref "D4") (pin "1") (pinfunction "K_1") (pintype "bidirectional"))
    )
    (net (code "25") (name "Net-(D7-CATHODE)") (class "Default")
      (node (ref "D7") (pin "1") (pinfunction "CATHODE_1") (pintype "bidirectional"))
      (node (ref "R_CAPACITOR") (pin "2") (pinfunction "2_2") (pintype "passive"))
    )
    (net (code "26") (name "Net-(EPD_C1-Pad1)") (class "Default")
      (node (ref "EPD_C1") (pin "1") (pinfunction "1_1") (pintype "passive"))
      (node (ref "J1") (pin "4") (pinfunction "4_4") (pintype "bidirectional"))
    )
    (net (code "27") (name "Net-(EPD_C2-Pad1)") (class "Default")
      (node (ref "EPD_C2") (pin "1") (pinfunction "1_1") (pintype "passive"))
      (node (ref "J1") (pin "5") (pinfunction "5_5") (pintype "bidirectional"))
    )
    (net (code "28") (name "Net-(EPD_C6-Pad1)") (class "Default")
      (node (ref "EPD_C6") (pin "1") (pinfunction "1_1") (pintype "passive"))
      (node (ref "J1") (pin "18") (pinfunction "18_18") (pintype "bidirectional"))
    )
    (net (code "29") (name "Net-(EPD_C7-Pad1)") (class "Default")
      (node (ref "EPD_C7") (pin "1") (pinfunction "1_1") (pintype "passive"))
      (node (ref "J1") (pin "19") (pinfunction "19_19") (pintype "bidirectional"))
    )
    (net (code "30") (name "Net-(EPD_C8-Pad1)") (class "Default")
      (node (ref "EPD_C8") (pin "1") (pinfunction "1_1") (pintype "passive"))
      (node (ref "J1") (pin "20") (pinfunction "20_20") (pintype "bidirectional"))
    )
    (net (code "31") (name "Net-(EPD_C10-Pad1)") (class "Default")
      (node (ref "EPD_C10") (pin "1") (pinfunction "1_1") (pintype "passive"))
      (node (ref "J1") (pin "22") (pinfunction "22_22") (pintype "bidirectional"))
    )
    (net (code "32") (name "Net-(EPD_C12-Pad1)") (class "Default")
      (node (ref "EPD_C12") (pin "1") (pinfunction "1_1") (pintype "passive"))
      (node (ref "J1") (pin "24") (pinfunction "24_24") (pintype "bidirectional"))
    )
    (net (code "33") (name "Net-(IC1-CT)") (class "Default")
      (node (ref "C_DELAY") (pin "1") (pinfunction "1_1") (pintype "passive"))
      (node (ref "IC1") (pin "5") (pinfunction "CT_5") (pintype "bidirectional"))
    )
    (net (code "34") (name "Net-(J2-PadA5)") (class "Default")
      (node (ref "J2") (pin "A5") (pinfunction "A5_A5") (pintype "bidirectional"))
      (node (ref "R2-USB1") (pin "2") (pinfunction "2_2") (pintype "passive"))
    )
    (net (code "35") (name "Net-(J2-PadB5)") (class "Default")
      (node (ref "J2") (pin "B5") (pinfunction "B5_B5") (pintype "bidirectional"))
      (node (ref "R2-USB") (pin "1") (pinfunction "1_1") (pintype "passive"))
    )
    (net (code "36") (name "Net-(MCP73831-PROG)") (class "Default")
      (node (ref "MCP73831") (pin "5") (pinfunction "PROG_5") (pintype "input"))
      (node (ref "R2_BAT") (pin "2") (pinfunction "2_2") (pintype "passive"))
    )
    (net (code "37") (name "Net-(MCP73831-STAT)") (class "Default")
      (node (ref "MCP73831") (pin "1") (pinfunction "STAT_1") (pintype "output"))
      (node (ref "R1_BAT") (pin "1") (pinfunction "1_1") (pintype "passive"))
    )
    (net (code "38") (name "PREVGH") (class "Default")
      (node (ref "D5") (pin "1") (pinfunction "K_1") (pintype "bidirectional"))
      (node (ref "EPD_C9") (pin "1") (pinfunction "1_1") (pintype "passive"))
      (node (ref "J1") (pin "21") (pinfunction "21_21") (pintype "bidirectional"))
    )
    (net (code "39") (name "PREVGL") (class "Default")
      (node (ref "D4") (pin "2") (pinfunction "A_2") (pintype "bidirectional"))
      (node (ref "EPD_C11") (pin "1") (pinfunction "1_1") (pintype "passive"))
      (node (ref "J1") (pin "23") (pinfunction "23_23") (pintype "bidirectional"))
    )
    (net (code "40") (name "RESE") (class "Default")
      (node (ref "J1") (pin "3") (pinfunction "3_3") (pintype "bidirectional"))
      (node (ref "Q3") (pin "2") (pinfunction "S_2") (pintype "bidirectional"))
      (node (ref "R3") (pin "1") (pinfunction "1_1") (pintype "passive"))
    )
    (net (code "41") (name "RESE'") (class "Default")
      (node (ref "R2") (pin "2") (pinfunction "2_2") (pintype "passive"))
      (node (ref "R3") (pin "2") (pinfunction "2_2") (pintype "passive"))
      (node (ref "SJ1") (pin "2") (pinfunction "2_2") (pintype "passive"))
    )
    (net (code "42") (name "RESET") (class "Default")
      (node (ref "C5") (pin "1") (pinfunction "1_1") (pintype "passive"))
      (node (ref "IC1") (pin "1") (pinfunction "VOUT_1") (pintype "bidirectional"))
      (node (ref "RESET_BUTTON") (pin "3") (pinfunction "3_3") (pintype "passive"))
      (node (ref "RESET_BUTTON") (pin "4") (pinfunction "4_4") (pintype "passive"))
      (node (ref "R_RESET") (pin "2") (pinfunction "2_2") (pintype "passive"))
      (node (ref "U2") (pin "3") (pinfunction "EN_3") (pintype "input"))
    )
    (net (code "43") (name "RTC_RST") (class "Default")
      (node (ref "U2") (pin "16") (pinfunction "IO18_16") (pintype "bidirectional"))
      (node (ref "U3") (pin "4") (pinfunction "~{RST}_4") (pintype "input"))
    )
    (net (code "44") (name "RX") (class "Default")
      (node (ref "TP2") (pin "TP") (pinfunction "TP_TP") (pintype "input"))
      (node (ref "U2") (pin "24") (pinfunction "RXD0/GPIO17_24") (pintype "bidirectional"))
    )
    (net (code "45") (name "SCK") (class "Default")
      (node (ref "D10") (pin "1") (pinfunction "1_1") (pintype "passive"))
      (node (ref "J1") (pin "13") (pinfunction "13_13") (pintype "bidirectional"))
      (node (ref "J4") (pin "P5") (pinfunction "CLK_P5") (pintype "bidirectional"))
      (node (ref "R6") (pin "1") (pinfunction "1_1") (pintype "passive"))
      (node (ref "TP8") (pin "TP") (pinfunction "TP_TP") (pintype "input"))
      (node (ref "U1") (pin "6") (pinfunction "CLK_6") (pintype "input"))
      (node (ref "U2") (pin "6") (pinfunction "IO6_6") (pintype "bidirectional"))
    )
    (net (code "46") (name "SCL") (class "Default")
      (node (ref "J3") (pin "4") (pinfunction "4_4") (pintype "passive"))
      (node (ref "R2-PINH") (pin "1") (pinfunction "1_1") (pintype "passive"))
      (node (ref "SENSOR2") (pin "4") (pinfunction "SCK_4") (pintype "input"))
      (node (ref "U2") (pin "20") (pinfunction "IO22_20") (pintype "bidirectional"))
      (node (ref "U3") (pin "16") (pinfunction "SCL_16") (pintype "input"))
      (node (ref "U4") (pin "7") (pinfunction "SCL_7") (pintype "input"))
    )
    (net (code "47") (name "SDA") (class "Default")
      (node (ref "J3") (pin "3") (pinfunction "3_3") (pintype "passive"))
      (node (ref "R1_PINH") (pin "1") (pinfunction "1_1") (pintype "passive"))
      (node (ref "SENSOR2") (pin "3") (pinfunction "SDI_3") (pintype "bidirectional"))
      (node (ref "U2") (pin "19") (pinfunction "IO21_19") (pintype "bidirectional"))
      (node (ref "U3") (pin "15") (pinfunction "SDA_15") (pintype "bidirectional"))
      (node (ref "U4") (pin "8") (pinfunction "SDA_8") (pintype "bidirectional"))
    )
    (net (code "48") (name "SRC") (class "Default")
      (node (ref "C4") (pin "2") (pinfunction "2_2") (pintype "passive"))
      (node (ref "D5") (pin "2") (pinfunction "A_2") (pintype "bidirectional"))
      (node (ref "L1") (pin "1") (pinfunction "1_1") (pintype "passive"))
      (node (ref "Q3") (pin "3") (pinfunction "D_3") (pintype "bidirectional"))
    )
    (net (code "49") (name "SS_SD") (class "Default")
      (node (ref "D8") (pin "1") (pinfunction "1_1") (pintype "passive"))
      (node (ref "J4") (pin "P2") (pinfunction "CD/DAT3_P2") (pintype "bidirectional"))
      (node (ref "R10") (pin "1") (pinfunction "1_1") (pintype "passive"))
      (node (ref "U2") (pin "4") (pinfunction "IO4_4") (pintype "bidirectional"))
    )
    (net (code "50") (name "TX") (class "Default")
      (node (ref "TP1") (pin "TP") (pinfunction "TP_TP") (pintype "input"))
      (node (ref "U2") (pin "25") (pinfunction "TXD0/GPIO16_25") (pintype "bidirectional"))
    )
    (net (code "51") (name "USB_D+") (class "Default")
      (node (ref "D1") (pin "1") (pinfunction "I/O1_1_1") (pintype "bidirectional"))
      (node (ref "U2") (pin "14") (pinfunction "IO13_14") (pintype "bidirectional"))
    )
    (net (code "52") (name "USB_D-") (class "Default")
      (node (ref "D1") (pin "3") (pinfunction "I/O2_1_3") (pintype "bidirectional"))
      (node (ref "U2") (pin "13") (pinfunction "IO12_13") (pintype "bidirectional"))
    )
    (net (code "53") (name "VBAT") (class "Default")
      (node (ref "C2_BAT") (pin "1") (pinfunction "1_1") (pintype "passive"))
      (node (ref "MCP73831") (pin "3") (pinfunction "VBAT_3") (pintype "power_in"))
      (node (ref "Q1") (pin "3") (pinfunction "D_3") (pintype "bidirectional"))
      (node (ref "TP3") (pin "TP") (pinfunction "TP_TP") (pintype "input"))
      (node (ref "U4") (pin "2") (pinfunction "CELL_2") (pintype "power_in"))
      (node (ref "U4") (pin "3") (pinfunction "VDD_3") (pintype "power_in"))
    )
    (net (code "54") (name "VBUS") (class "Default")
      (node (ref "C1_BAT") (pin "1") (pinfunction "1_1") (pintype "passive"))
      (node (ref "C4_USB") (pin "1") (pinfunction "1_1") (pintype "passive"))
      (node (ref "C5_USB") (pin "1") (pinfunction "1_1") (pintype "passive"))
      (node (ref "CHG_LED") (pin "A") (pinfunction "A_A") (pintype "passive"))
      (node (ref "D1") (pin "5") (pinfunction "VBUS_5") (pintype "bidirectional"))
      (node (ref "D2") (pin "2") (pinfunction "ANODE_2") (pintype "bidirectional"))
      (node (ref "MCP73831") (pin "4") (pinfunction "VIN_4") (pintype "power_in"))
      (node (ref "PFMF.050.1") (pin "2") (pinfunction "2_2") (pintype "passive"))
      (node (ref "Q1") (pin "1") (pinfunction "G_1") (pintype "bidirectional"))
      (node (ref "R1_PWRUSB") (pin "2") (pinfunction "2_2") (pintype "passive"))
      (node (ref "TP14") (pin "TP") (pinfunction "TP_TP") (pintype "input"))
    )
    (net (code "55") (name "VRTC") (class "Default")
      (node (ref "C10_SUPERCAP") (pin "2") (pinfunction "2_2") (pintype "passive"))
      (node (ref "C8") (pin "1") (pinfunction "1_1") (pintype "passive"))
      (node (ref "R_CAPACITOR") (pin "1") (pinfunction "1_1") (pintype "passive"))
      (node (ref "U3") (pin "14") (pinfunction "VBAT_14") (pintype "power_in"))
    )
    (net (code "56") (name "VUSB") (class "Default")
      (node (ref "J2") (pin "A4") (pinfunction "A4_A4") (pintype "bidirectional"))
      (node (ref "J2") (pin "A9") (pinfunction "A9_A9") (pintype "bidirectional"))
      (node (ref "J2") (pin "B4") (pinfunction "B4_B4") (pintype "bidirectional"))
      (node (ref "J2") (pin "B9") (pinfunction "B9_B9") (pintype "bidirectional"))
      (node (ref "PFMF.050.1") (pin "1") (pinfunction "1_1") (pintype "passive"))
    )
    (net (code "57") (name "unconnected-(IC1-NC-Pad4)") (class "Default")
      (node (ref "IC1") (pin "4") (pinfunction "NC_4") (pintype "no_connect"))
    )
    (net (code "58") (name "unconnected-(IC4-NC-Pad4)") (class "Default")
      (node (ref "IC4") (pin "4") (pinfunction "NC_4") (pintype "no_connect"))
    )
    (net (code "59") (name "unconnected-(J1-Pad1)") (class "Default")
      (node (ref "J1") (pin "1") (pinfunction "1_1") (pintype "bidirectional"))
    )
    (net (code "60") (name "unconnected-(J1-Pad6)") (class "Default")
      (node (ref "J1") (pin "6") (pinfunction "6_6") (pintype "bidirectional"))
    )
    (net (code "61") (name "unconnected-(J1-Pad7)") (class "Default")
      (node (ref "J1") (pin "7") (pinfunction "7_7") (pintype "bidirectional"))
    )
    (net (code "62") (name "unconnected-(J2-PadA8)") (class "Default")
      (node (ref "J2") (pin "A8") (pinfunction "A8_A8") (pintype "bidirectional"))
    )
    (net (code "63") (name "unconnected-(J2-PadB8)") (class "Default")
      (node (ref "J2") (pin "B8") (pinfunction "B8_B8") (pintype "bidirectional"))
    )
    (net (code "64") (name "unconnected-(J4-DAT1-PadP8)") (class "Default")
      (node (ref "J4") (pin "P8") (pinfunction "DAT1_P8") (pintype "bidirectional"))
    )
    (net (code "65") (name "unconnected-(J4-DAT2-PadP1)") (class "Default")
      (node (ref "J4") (pin "P1") (pinfunction "DAT2_P1") (pintype "bidirectional"))
    )
    (net (code "66") (name "unconnected-(J4-DETECTION_1-PadS1)") (class "Default")
      (node (ref "J4") (pin "S1") (pinfunction "DETECTION_1_S1") (pintype "bidirectional"))
    )
    (net (code "67") (name "unconnected-(J4-DETECTION_2-PadS2)") (class "Default")
      (node (ref "J4") (pin "S2") (pinfunction "DETECTION_2_S2") (pintype "bidirectional"))
    )
    (net (code "68") (name "unconnected-(U2-NC-Pad22)") (class "Default")
      (node (ref "U2") (pin "22") (pinfunction "NC_22") (pintype "no_connect"))
    )
    (net (code "69") (name "unconnected-(U4-~{ALERT}-Pad5)") (class "Default")
      (node (ref "U4") (pin "5") (pinfunction "~{ALERT}_5") (pintype "output"))
    )
  )
)
